# Input.net
KiCad netlist of a schematic drawn in Altium Designer
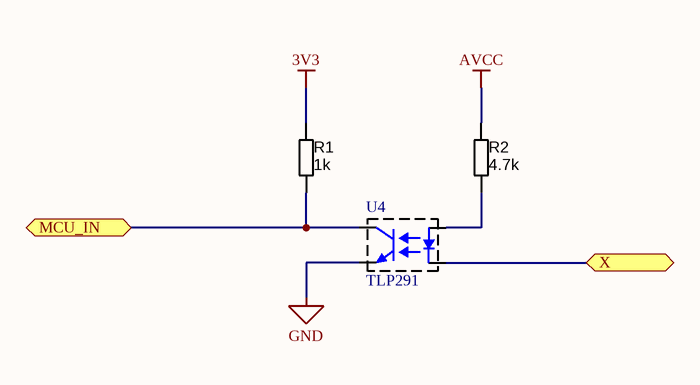
[diagram p0: Input.SchDoc]

(export (version "E")
  (design (tool "Eeschema 10.0.6"))
  (components
    (comp (ref "R1")
      (value "1k")
      (footprint "IPC-7352 Chip_Resistor_N:RESC1608N")
      (description "Resistor SMD chip")
      (fields (field (name "TOLERANCE") "?%"))
      (libsource (lib "LCR Devices") (part "Resistor SMD chip"))
    )
    (comp (ref "R2")
      (value "4.7k")
      (footprint "IPC-7352 Chip_Resistor_N:RESC1608N")
      (description "Resistor SMD chip")
      (fields (field (name "TOLERANCE") "?%"))
      (libsource (lib "LCR Devices") (part "Resistor SMD chip"))
    )
    (comp (ref "U4")
      (value "TLP291")
      (footprint "Transistors:SO4_N")
      (description "Optoisolator Transistor Output 3750Vrms 1 Channel 4-SO")
      (libsource (lib "Transistors") (part "TLP291"))
    )
  )
  (nets
    (net (code "1") (name "/MCU_IN") (class "Default")
      (node (ref "R1") (pin "2") (pinfunction "2_2") (pintype "passive"))
      (node (ref "U4") (pin "4") (pinfunction "COLLECTOR_4") (pintype "passive"))
    )
    (net (code "2") (name "/X") (class "Default")
      (node (ref "U4") (pin "2") (pinfunction "CATHODE_2") (pintype "passive"))
    )
    (net (code "3") (name "3V3") (class "Default")
      (node (ref "R1") (pin "1") (pinfunction "1_1") (pintype "passive"))
    )
    (net (code "4") (name "AVCC") (class "Default")
      (node (ref "R2") (pin "1") (pinfunction "1_1") (pintype "passive"))
    )
    (net (code "5") (name "GND") (class "Default")
      (node (ref "U4") (pin "3") (pinfunction "EMITTER_3") (pintype "passive"))
    )
    (net (code "6") (name "Net-(U4-ANODE)") (class "Default")
      (node (ref "R2") (pin "2") (pinfunction "2_2") (pintype "passive"))
      (node (ref "U4") (pin "1") (pinfunction "ANODE_1") (pintype "passive"))
    )
  )
)
